# VBAT_to_12V.net
KiCad netlist of a schematic drawn in Altium Designer
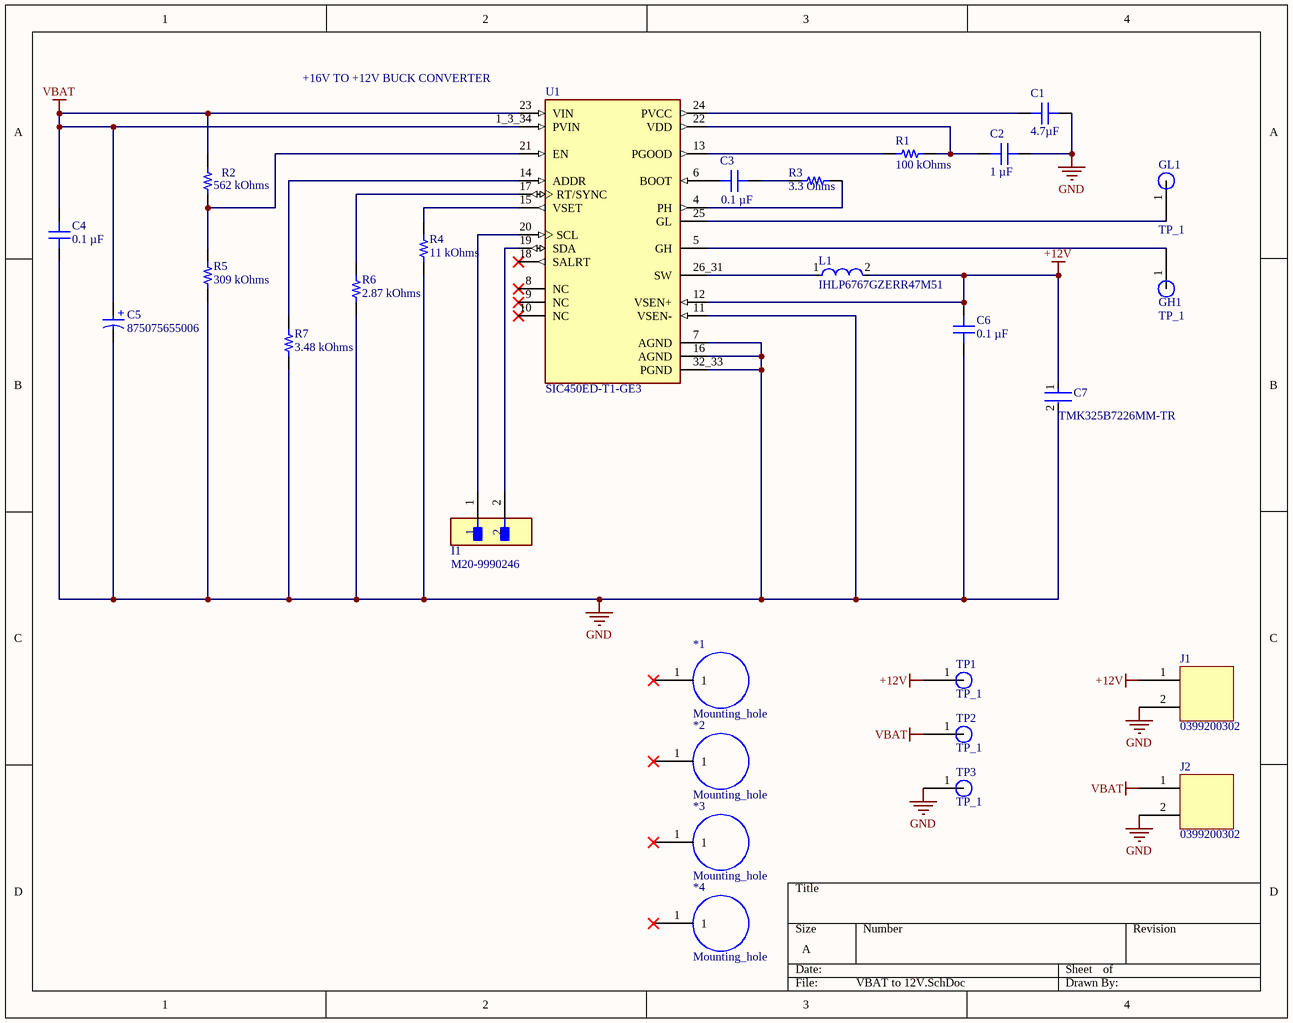
[diagram p0: VBAT to 12V.SchDoc]

(export (version "E")
  (design (tool "Eeschema 10.0.6"))
  (components
    (comp (ref "*1")
      (value "Mounting_hole")
      (footprint "Mounting_Hole")
      (libsource (lib "Seaglider_Power_board_Schematic_Library") (part "Mounting_hole"))
    )
    (comp (ref "*2")
      (value "Mounting_hole")
      (footprint "Mounting_Hole")
      (libsource (lib "Seaglider_Power_board_Schematic_Library") (part "Mounting_hole"))
    )
    (comp (ref "*3")
      (value "Mounting_hole")
      (footprint "Mounting_Hole")
      (libsource (lib "Seaglider_Power_board_Schematic_Library") (part "Mounting_hole"))
    )
    (comp (ref "*4")
      (value "Mounting_hole")
      (footprint "Mounting_Hole")
      (libsource (lib "Seaglider_Power_board_Schematic_Library") (part "Mounting_hole"))
    )
    (comp (ref "C1")
      (value "4.7µF")
      (footprint "CAP 0603_1608")
      (description "CAP CER 4.7UF 6.3V X5R 0603")
      (fields (field (name "PART NUMBER") "06036D475KAT4A") (field (name "MANUFACTURER") "AVX Corporation"))
      (libsource (lib "Celestial Altium Library - altium_library (2)") (part "Capacitor"))
    )
    (comp (ref "C2")
      (value "1 µF")
      (footprint "CAP 0603_1608")
      (description "CAP CER 1UF 6.3V X7R 0603")
      (fields (field (name "PART NUMBER") "C0603X105M9RACAUTO") (field (name "MANUFACTURER") "KEMET"))
      (libsource (lib "Celestial Altium Library - altium_library (2)") (part "Capacitor"))
    )
    (comp (ref "C3")
      (value "0.1 µF")
      (footprint "CAP 0402_1005")
      (description "CAP CER 100NF 10V X7R 0402")
      (fields
        (field (name "PART NUMBER") "CL05B104KP5VPNC")
        (field (name "MANUFACTURER") "Samsung Electro-Mechanics")
      )
      (libsource (lib "Celestial Altium Library - altium_library (2)") (part "Capacitor"))
    )
    (comp (ref "C4")
      (value "0.1 µF")
      (footprint "CAP 0402_1005")
      (description "CAP CER 0.1UF 25V X7R 0402")
      (fields
        (field (name "PART NUMBER") "GCM155R71E104KE02D")
        (field (name "MANUFACTURER") "Murata Electronics")
      )
      (libsource (lib "Celestial Altium Library - altium_library (2)") (part "Capacitor"))
    )
    (comp (ref "C5")
      (value "875075655006")
      (footprint "WCAP-PSLC_D8H11.7")
      (description "875075655006 Cap, 150Uf, 35V, Alu Elec Smd, Polymer Rohs Compliant: Yes")
      (libsource (lib "Altium Content Vault") (part "Capacitor_Polarized"))
    )
    (comp (ref "C6")
      (value "0.1 µF")
      (footprint "CAP 0402_1005")
      (description "CAP CER 0.1UF 25V X7R 0402")
      (fields
        (field (name "PART NUMBER") "GCM155R71E104KE02D")
        (field (name "MANUFACTURER") "Murata Electronics")
      )
      (libsource (lib "Celestial Altium Library - altium_library (2)") (part "Capacitor"))
    )
    (comp (ref "C7")
      (value "TMK325B7226MM-TR")
      (footprint "FP-1210-L_3_2_0_3-W_2_5_0-MFG")
      (description "CAP CER 22UF 25V X7R 1210")
      (fields (field (name "TOLERANCE") "20%") (field (name "VOLTAGE") "25V"))
      (libsource (lib "Altium Content Vault") (part "b4654b650e69147ec39a6b967a45e02"))
    )
    (comp (ref "GH1")
      (value "TP_1")
      (footprint "Test_point1")
      (libsource (lib "Seaglider_Power_board_Schematic_Library") (part "Test_point1"))
    )
    (comp (ref "GL1")
      (value "TP_1")
      (footprint "Test_point1")
      (libsource (lib "Seaglider_Power_board_Schematic_Library") (part "Test_point1"))
    )
    (comp (ref "I1")
      (value "M20-9990246")
      (footprint "FP-M20-9990246-MFG")
      (description "CONN HEADER VERT 2POS 2.54MM")
      (fields
        (field (name "OCTOPART") "https://octopart.com/m20-9990246-harwin-2590635")
        (field (name "MANUFACTURER") "Harwin")
      )
      (libsource (lib "Altium Content Vault") (part "3bc925449376181038e59eaffc5286c"))
    )
    (comp (ref "J1")
      (value "0399200302")
      (footprint "0399200302")
      (libsource (lib "Seaglider_Power_board_Schematic_Library") (part "0399200302"))
    )
    (comp (ref "J2")
      (value "0399200302")
      (footprint "0399200302")
      (libsource (lib "Seaglider_Power_board_Schematic_Library") (part "0399200302"))
    )
    (comp (ref "L1")
      (value "IHLP6767GZERR47M51")
      (footprint "FP-IHLP-6767GZ-FP_3_825x1-MFG")
      (description "Commercial Inductors, High Temperature (155 °C) Series 0.47uH 65A 0.95mΩ 20%")
      (fields (field (name "TOLERANCE") "20%"))
      (libsource (lib "Altium Content Vault") (part "725321dda6339637d4d059423bc1c3c"))
    )
    (comp (ref "R1")
      (value "100 kOhms")
      (footprint "RES 0402_1005")
      (description "RES SMD 100K OHM 1% 1/16W 0402")
      (fields (field (name "PART NUMBER") "RT0402FRE07100KL") (field (name "MANUFACTURER") "Yageo"))
      (libsource (lib "Celestial Altium Library - altium_library (2)") (part "Resistor"))
    )
    (comp (ref "R2")
      (value "562 kOhms")
      (footprint "RES 0603_1608")
      (description "RES 562K OHM 1% 1/10W 0603")
      (fields
        (field (name "PART NUMBER") "RK73H1JTTD5623F")
        (field (name "MANUFACTURER") "KOA Speer Electronics, Inc.")
      )
      (libsource (lib "Celestial Altium Library - altium_library (2)") (part "Resistor"))
    )
    (comp (ref "R3")
      (value "3.3 Ohms")
      (footprint "RES 0402_1005")
      (description "RES SMD 3.3 OHM 5% 1/10W 0402")
      (fields
        (field (name "PART NUMBER") "ERJ-2GEJ3R3X")
        (field (name "MANUFACTURER") "Panasonic Electronic Components")
      )
      (libsource (lib "Celestial Altium Library - altium_library (2)") (part "Resistor"))
    )
    (comp (ref "R4")
      (value "11 kOhms")
      (footprint "RES 0603_1608")
      (description "RES 11K OHM 0.1% 1/10W 0603")
      (fields (field (name "PART NUMBER") "TNPW060311K0BYEN") (field (name "MANUFACTURER") "Vishay Dale"))
      (libsource (lib "Celestial Altium Library - altium_library (2)") (part "Resistor"))
    )
    (comp (ref "R5")
      (value "309 kOhms")
      (footprint "RES 0603_1608")
      (description "RES SMD 309K OHM 0.1% 1/10W 0603")
      (fields (field (name "PART NUMBER") "RG1608P-3093-B-T5") (field (name "MANUFACTURER") "Susumu"))
      (libsource (lib "Celestial Altium Library - altium_library (2)") (part "Resistor"))
    )
    (comp (ref "R6")
      (value "2.87 kOhms")
      (footprint "RES 0603_1608")
      (description "RES 2.87K OHM 1% 1/10W 0603")
      (fields (field (name "PART NUMBER") "RC0603FR-072K87L") (field (name "MANUFACTURER") "Yageo"))
      (libsource (lib "Celestial Altium Library - altium_library (2)") (part "Resistor"))
    )
    (comp (ref "R7")
      (value "3.48 kOhms")
      (footprint "RES 0603_1608")
      (description "RES 3.48K OHM 1% 1/8W 0603")
      (fields
        (field (name "PART NUMBER") "RNCP0603FTD3K48")
        (field (name "MANUFACTURER") "Stackpole Electronics Inc")
      )
      (libsource (lib "Celestial Altium Library - altium_library (2)") (part "Resistor"))
    )
    (comp (ref "TP1")
      (value "TP_1")
      (footprint "Test_point1")
      (libsource (lib "Seaglider_Power_board_Schematic_Library") (part "Test_point1"))
    )
    (comp (ref "TP2")
      (value "TP_1")
      (footprint "Test_point1")
      (libsource (lib "Seaglider_Power_board_Schematic_Library") (part "Test_point1"))
    )
    (comp (ref "TP3")
      (value "TP_1")
      (footprint "Test_point1")
      (libsource (lib "Seaglider_Power_board_Schematic_Library") (part "Test_point1"))
    )
    (comp (ref "U1")
      (value "SIC450ED-T1-GE3")
      (footprint "VREG_SIC450ED-T1-GE3")
      (description "Buck Switching Regulator IC Positive Adjustable 0.3V 1 Output 40A 34-PowerWFQFN")
      (fields (field (name "MF") "Vishay Siliconix"))
      (libsource (lib "Americas- Environmental Engineering Club- University of Victoria") (part "SIC450ED-T1-GE3"))
    )
  )
  (nets
    (net (code "1") (name "+12V") (class "Default")
      (node (ref "C6") (pin "2") (pinfunction "2_2") (pintype "passive"))
      (node (ref "C7") (pin "1") (pinfunction "1_1") (pintype "passive"))
      (node (ref "J1") (pin "1") (pintype "passive"))
      (node (ref "L1") (pin "2") (pinfunction "2_2") (pintype "passive"))
      (node (ref "TP1") (pin "1") (pintype "passive"))
      (node (ref "U1") (pin "12") (pinfunction "VSEN+_12") (pintype "input"))
    )
    (net (code "2") (name "GND") (class "Default")
      (node (ref "C1") (pin "1") (pinfunction "1_1") (pintype "passive"))
      (node (ref "C2") (pin "1") (pinfunction "1_1") (pintype "passive"))
      (node (ref "C4") (pin "1") (pinfunction "1_1") (pintype "passive"))
      (node (ref "C5") (pin "2") (pinfunction "N_2") (pintype "passive"))
      (node (ref "C6") (pin "1") (pinfunction "1_1") (pintype "passive"))
      (node (ref "C7") (pin "2") (pinfunction "2_2") (pintype "passive"))
      (node (ref "J1") (pin "2") (pintype "passive"))
      (node (ref "J2") (pin "2") (pintype "passive"))
      (node (ref "R4") (pin "1") (pinfunction "1_1") (pintype "passive"))
      (node (ref "R5") (pin "1") (pinfunction "1_1") (pintype "passive"))
      (node (ref "R6") (pin "1") (pinfunction "1_1") (pintype "passive"))
      (node (ref "R7") (pin "1") (pinfunction "1_1") (pintype "passive"))
      (node (ref "TP3") (pin "1") (pintype "passive"))
      (node (ref "U1") (pin "11") (pinfunction "VSEN-_11") (pintype "input"))
      (node (ref "U1") (pin "16") (pinfunction "AGND_16") (pintype "power_in"))
      (node (ref "U1") (pin "32_33") (pinfunction "PGND_32_33") (pintype "power_in"))
      (node (ref "U1") (pin "7") (pinfunction "AGND_7") (pintype "power_in"))
    )
    (net (code "3") (name "Net-(C3-Pad2)") (class "Default")
      (node (ref "C3") (pin "2") (pinfunction "2_2") (pintype "passive"))
      (node (ref "R3") (pin "1") (pinfunction "1_1") (pintype "passive"))
    )
    (net (code "4") (name "Net-(U1-ADDR)") (class "Default")
      (node (ref "R7") (pin "2") (pinfunction "2_2") (pintype "passive"))
      (node (ref "U1") (pin "14") (pinfunction "ADDR_14") (pintype "input"))
    )
    (net (code "5") (name "Net-(U1-BOOT)") (class "Default")
      (node (ref "C3") (pin "1") (pinfunction "1_1") (pintype "passive"))
      (node (ref "U1") (pin "6") (pinfunction "BOOT_6") (pintype "input"))
    )
    (net (code "6") (name "Net-(U1-EN)") (class "Default")
      (node (ref "R2") (pin "1") (pinfunction "1_1") (pintype "passive"))
      (node (ref "R5") (pin "2") (pinfunction "2_2") (pintype "passive"))
      (node (ref "U1") (pin "21") (pinfunction "EN_21") (pintype "input"))
    )
    (net (code "7") (name "Net-(U1-GH)") (class "Default")
      (node (ref "GH1") (pin "1") (pintype "passive"))
      (node (ref "U1") (pin "5") (pinfunction "GH_5") (pintype "passive"))
    )
    (net (code "8") (name "Net-(U1-GL)") (class "Default")
      (node (ref "GL1") (pin "1") (pintype "passive"))
      (node (ref "U1") (pin "25") (pinfunction "GL_25") (pintype "passive"))
    )
    (net (code "9") (name "Net-(U1-PGOOD)") (class "Default")
      (node (ref "R1") (pin "2") (pinfunction "2_2") (pintype "passive"))
      (node (ref "U1") (pin "13") (pinfunction "PGOOD_13") (pintype "output"))
    )
    (net (code "10") (name "Net-(U1-PH)") (class "Default")
      (node (ref "R3") (pin "2") (pinfunction "2_2") (pintype "passive"))
      (node (ref "U1") (pin "4") (pinfunction "PH_4") (pintype "output"))
    )
    (net (code "11") (name "Net-(U1-PVCC)") (class "Default")
      (node (ref "C1") (pin "2") (pinfunction "2_2") (pintype "passive"))
      (node (ref "U1") (pin "24") (pinfunction "PVCC_24") (pintype "output"))
    )
    (net (code "12") (name "Net-(U1-RT{slash}SYNC)") (class "Default")
      (node (ref "R6") (pin "2") (pinfunction "2_2") (pintype "passive"))
      (node (ref "U1") (pin "17") (pinfunction "RT/SYNC_17") (pintype "bidirectional"))
    )
    (net (code "13") (name "Net-(U1-SCL)") (class "Default")
      (node (ref "I1") (pin "1") (pinfunction "1_1") (pintype "passive"))
      (node (ref "U1") (pin "20") (pinfunction "SCL_20") (pintype "input"))
    )
    (net (code "14") (name "Net-(U1-SDA)") (class "Default")
      (node (ref "I1") (pin "2") (pinfunction "2_2") (pintype "passive"))
      (node (ref "U1") (pin "19") (pinfunction "SDA_19") (pintype "bidirectional"))
    )
    (net (code "15") (name "Net-(U1-SW)") (class "Default")
      (node (ref "L1") (pin "1") (pinfunction "1_1") (pintype "passive"))
      (node (ref "U1") (pin "26_31") (pinfunction "SW_26_31") (pintype "passive"))
    )
    (net (code "16") (name "Net-(U1-VDD)") (class "Default")
      (node (ref "C2") (pin "2") (pinfunction "2_2") (pintype "passive"))
      (node (ref "R1") (pin "1") (pinfunction "1_1") (pintype "passive"))
      (node (ref "U1") (pin "22") (pinfunction "VDD_22") (pintype "output"))
    )
    (net (code "17") (name "Net-(U1-VSET)") (class "Default")
      (node (ref "R4") (pin "2") (pinfunction "2_2") (pintype "passive"))
      (node (ref "U1") (pin "15") (pinfunction "VSET_15") (pintype "output"))
    )
    (net (code "18") (name "VBAT") (class "Default")
      (node (ref "C4") (pin "2") (pinfunction "2_2") (pintype "passive"))
      (node (ref "C5") (pin "1") (pinfunction "P_1") (pintype "passive"))
      (node (ref "J2") (pin "1") (pintype "passive"))
      (node (ref "R2") (pin "2") (pinfunction "2_2") (pintype "passive"))
      (node (ref "TP2") (pin "1") (pintype "passive"))
      (node (ref "U1") (pin "1_3_34") (pinfunction "PVIN_1_3_34") (pintype "input"))
      (node (ref "U1") (pin "23") (pinfunction "VIN_23") (pintype "input"))
    )
    (net (code "19") (name "unconnected-(*1-Pad1)") (class "Default")
      (node (ref "*1") (pin "1") (pinfunction "1_1") (pintype "passive+no_connect"))
    )
    (net (code "20") (name "unconnected-(*2-Pad1)") (class "Default")
      (node (ref "*2") (pin "1") (pinfunction "1_1") (pintype "passive+no_connect"))
    )
    (net (code "21") (name "unconnected-(*3-Pad1)") (class "Default")
      (node (ref "*3") (pin "1") (pinfunction "1_1") (pintype "passive+no_connect"))
    )
    (net (code "22") (name "unconnected-(*4-Pad1)") (class "Default")
      (node (ref "*4") (pin "1") (pinfunction "1_1") (pintype "passive+no_connect"))
    )
    (net (code "23") (name "unconnected-(U1-NC-Pad8)") (class "Default")
      (node (ref "U1") (pin "8") (pinfunction "NC_8") (pintype "passive+no_connect"))
    )
    (net (code "24") (name "unconnected-(U1-NC-Pad9)") (class "Default")
      (node (ref "U1") (pin "9") (pinfunction "NC_9") (pintype "passive+no_connect"))
    )
    (net (code "25") (name "unconnected-(U1-NC-Pad10)") (class "Default")
      (node (ref "U1") (pin "10") (pinfunction "NC_10") (pintype "passive+no_connect"))
    )
    (net (code "26") (name "unconnected-(U1-SALRT-Pad18)") (class "Default")
      (node (ref "U1") (pin "18") (pinfunction "SALRT_18") (pintype "output+no_connect"))
    )
  )
)
